# MCU_IO.net
KiCad netlist of a schematic drawn in Altium Designer
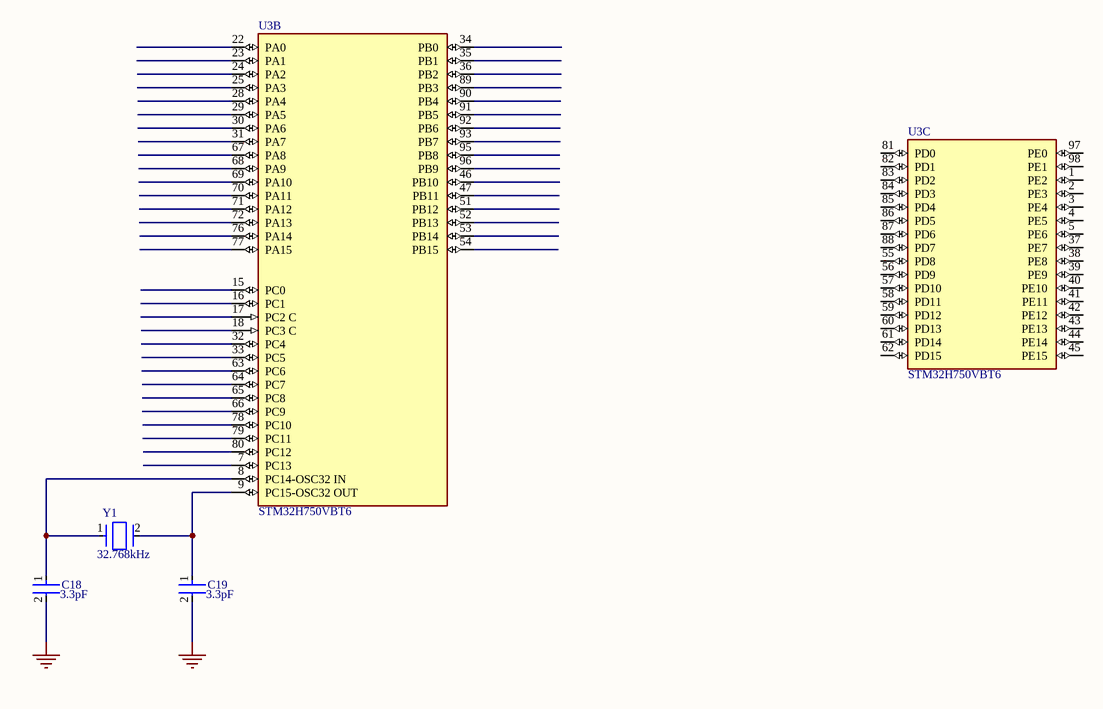
[diagram p0: MCU_IO.SchDoc]

(export (version "E")
  (design (tool "Eeschema 10.0.6"))
  (components
    (comp (ref "C18")
      (value "GCM1555C1H3R3CA16J")
      (footprint "FP-GCM155-0_05-IPC_C")
      (description "Ceramic Capacitor for Automotive 3.3pF ±0.25pF 50VDC C0G 0402 Paper T/R")
      (fields (field (name "CAPACITANCE") "3.3pF"))
      (libsource (lib "Altium Content Vault") (part "02cd4be3c70576c341d710602a673aa"))
    )
    (comp (ref "C19")
      (value "GCM1555C1H3R3CA16J")
      (footprint "FP-GCM155-0_05-IPC_C")
      (description "Ceramic Capacitor for Automotive 3.3pF ±0.25pF 50VDC C0G 0402 Paper T/R")
      (fields (field (name "CAPACITANCE") "3.3pF"))
      (libsource (lib "Altium Content Vault") (part "02cd4be3c70576c341d710602a673aa"))
    )
    (comp (ref "U3")
      (value "STM32H750VBT6")
      (footprint "FP-LQFP100-1L-MFG")
      (description "IC MCU 32BIT 128KB FLASH 100LQFP")
      (fields
        (field (name "OCTOPART") "https://octopart.com/stm32h750vbt6-stmicroelectronics-94048547")
        (field (name "MANUFACTURER") "STMicroelectronics")
      )
      (libsource (lib "Altium Content Vault") (part "aca449acb2b80670ba40d015d68dc7a"))
    )
    (comp (ref "Y1")
      (value "ECS-.327-6-34QCN-TR")
      (footprint "FP-ECX-34Q-MFG")
      (description "CRYSTAL 32.768KHZ 6PF SMD")
      (fields
        (field (name "OCTOPART") "https://octopart.com/ecs-.327-6-34qcn-tr-ecs+international-97157707")
        (field (name "MANUFACTURER") "ECS Inc.")
        (field (name "FREQUENCY") "32.768kHz")
      )
      (libsource (lib "Altium Content Vault") (part "99724985039315a44fd0d1401b84e49"))
    )
  )
  (nets
    (net (code "1") (name "GND") (class "Default")
      (node (ref "C18") (pin "2") (pinfunction "2_2") (pintype "passive"))
      (node (ref "C19") (pin "2") (pinfunction "2_2") (pintype "passive"))
    )
    (net (code "2") (name "Net-(U3B-PC14-OSC32_IN)") (class "Default")
      (node (ref "C18") (pin "1") (pinfunction "1_1") (pintype "passive"))
      (node (ref "U3") (pin "8") (pinfunction "PC14-OSC32_IN_8") (pintype "bidirectional"))
      (node (ref "Y1") (pin "1") (pinfunction "In/Out_1") (pintype "passive"))
    )
    (net (code "3") (name "Net-(U3B-PC15-OSC32_OUT)") (class "Default")
      (node (ref "C19") (pin "1") (pinfunction "1_1") (pintype "passive"))
      (node (ref "U3") (pin "9") (pinfunction "PC15-OSC32_OUT_9") (pintype "bidirectional"))
      (node (ref "Y1") (pin "2") (pinfunction "Out/In_2") (pintype "passive"))
    )
    (net (code "4") (name "unconnected-(U3B-PA0-Pad22)") (class "Default")
      (node (ref "U3") (pin "22") (pinfunction "PA0_22") (pintype "bidirectional"))
    )
    (net (code "5") (name "unconnected-(U3B-PA1-Pad23)") (class "Default")
      (node (ref "U3") (pin "23") (pinfunction "PA1_23") (pintype "bidirectional"))
    )
    (net (code "6") (name "unconnected-(U3B-PA2-Pad24)") (class "Default")
      (node (ref "U3") (pin "24") (pinfunction "PA2_24") (pintype "bidirectional"))
    )
    (net (code "7") (name "unconnected-(U3B-PA3-Pad25)") (class "Default")
      (node (ref "U3") (pin "25") (pinfunction "PA3_25") (pintype "bidirectional"))
    )
    (net (code "8") (name "unconnected-(U3B-PA4-Pad28)") (class "Default")
      (node (ref "U3") (pin "28") (pinfunction "PA4_28") (pintype "bidirectional"))
    )
    (net (code "9") (name "unconnected-(U3B-PA5-Pad29)") (class "Default")
      (node (ref "U3") (pin "29") (pinfunction "PA5_29") (pintype "bidirectional"))
    )
    (net (code "10") (name "unconnected-(U3B-PA6-Pad30)") (class "Default")
      (node (ref "U3") (pin "30") (pinfunction "PA6_30") (pintype "bidirectional"))
    )
    (net (code "11") (name "unconnected-(U3B-PA7-Pad31)") (class "Default")
      (node (ref "U3") (pin "31") (pinfunction "PA7_31") (pintype "bidirectional"))
    )
    (net (code "12") (name "unconnected-(U3B-PA8-Pad67)") (class "Default")
      (node (ref "U3") (pin "67") (pinfunction "PA8_67") (pintype "bidirectional"))
    )
    (net (code "13") (name "unconnected-(U3B-PA9-Pad68)") (class "Default")
      (node (ref "U3") (pin "68") (pinfunction "PA9_68") (pintype "bidirectional"))
    )
    (net (code "14") (name "unconnected-(U3B-PA10-Pad69)") (class "Default")
      (node (ref "U3") (pin "69") (pinfunction "PA10_69") (pintype "bidirectional"))
    )
    (net (code "15") (name "unconnected-(U3B-PA11-Pad70)") (class "Default")
      (node (ref "U3") (pin "70") (pinfunction "PA11_70") (pintype "bidirectional"))
    )
    (net (code "16") (name "unconnected-(U3B-PA12-Pad71)") (class "Default")
      (node (ref "U3") (pin "71") (pinfunction "PA12_71") (pintype "bidirectional"))
    )
    (net (code "17") (name "unconnected-(U3B-PA13-Pad72)") (class "Default")
      (node (ref "U3") (pin "72") (pinfunction "PA13_72") (pintype "bidirectional"))
    )
    (net (code "18") (name "unconnected-(U3B-PA14-Pad76)") (class "Default")
      (node (ref "U3") (pin "76") (pinfunction "PA14_76") (pintype "bidirectional"))
    )
    (net (code "19") (name "unconnected-(U3B-PA15-Pad77)") (class "Default")
      (node (ref "U3") (pin "77") (pinfunction "PA15_77") (pintype "bidirectional"))
    )
    (net (code "20") (name "unconnected-(U3B-PB0-Pad34)") (class "Default")
      (node (ref "U3") (pin "34") (pinfunction "PB0_34") (pintype "bidirectional"))
    )
    (net (code "21") (name "unconnected-(U3B-PB1-Pad35)") (class "Default")
      (node (ref "U3") (pin "35") (pinfunction "PB1_35") (pintype "bidirectional"))
    )
    (net (code "22") (name "unconnected-(U3B-PB2-Pad36)") (class "Default")
      (node (ref "U3") (pin "36") (pinfunction "PB2_36") (pintype "bidirectional"))
    )
    (net (code "23") (name "unconnected-(U3B-PB3-Pad89)") (class "Default")
      (node (ref "U3") (pin "89") (pinfunction "PB3_89") (pintype "bidirectional"))
    )
    (net (code "24") (name "unconnected-(U3B-PB4-Pad90)") (class "Default")
      (node (ref "U3") (pin "90") (pinfunction "PB4_90") (pintype "bidirectional"))
    )
    (net (code "25") (name "unconnected-(U3B-PB5-Pad91)") (class "Default")
      (node (ref "U3") (pin "91") (pinfunction "PB5_91") (pintype "bidirectional"))
    )
    (net (code "26") (name "unconnected-(U3B-PB6-Pad92)") (class "Default")
      (node (ref "U3") (pin "92") (pinfunction "PB6_92") (pintype "bidirectional"))
    )
    (net (code "27") (name "unconnected-(U3B-PB7-Pad93)") (class "Default")
      (node (ref "U3") (pin "93") (pinfunction "PB7_93") (pintype "bidirectional"))
    )
    (net (code "28") (name "unconnected-(U3B-PB8-Pad95)") (class "Default")
      (node (ref "U3") (pin "95") (pinfunction "PB8_95") (pintype "bidirectional"))
    )
    (net (code "29") (name "unconnected-(U3B-PB9-Pad96)") (class "Default")
      (node (ref "U3") (pin "96") (pinfunction "PB9_96") (pintype "bidirectional"))
    )
    (net (code "30") (name "unconnected-(U3B-PB10-Pad46)") (class "Default")
      (node (ref "U3") (pin "46") (pinfunction "PB10_46") (pintype "bidirectional"))
    )
    (net (code "31") (name "unconnected-(U3B-PB11-Pad47)") (class "Default")
      (node (ref "U3") (pin "47") (pinfunction "PB11_47") (pintype "bidirectional"))
    )
    (net (code "32") (name "unconnected-(U3B-PB12-Pad51)") (class "Default")
      (node (ref "U3") (pin "51") (pinfunction "PB12_51") (pintype "bidirectional"))
    )
    (net (code "33") (name "unconnected-(U3B-PB13-Pad52)") (class "Default")
      (node (ref "U3") (pin "52") (pinfunction "PB13_52") (pintype "bidirectional"))
    )
    (net (code "34") (name "unconnected-(U3B-PB14-Pad53)") (class "Default")
      (node (ref "U3") (pin "53") (pinfunction "PB14_53") (pintype "bidirectional"))
    )
    (net (code "35") (name "unconnected-(U3B-PB15-Pad54)") (class "Default")
      (node (ref "U3") (pin "54") (pinfunction "PB15_54") (pintype "bidirectional"))
    )
    (net (code "36") (name "unconnected-(U3B-PC0-Pad15)") (class "Default")
      (node (ref "U3") (pin "15") (pinfunction "PC0_15") (pintype "bidirectional"))
    )
    (net (code "37") (name "unconnected-(U3B-PC1-Pad16)") (class "Default")
      (node (ref "U3") (pin "16") (pinfunction "PC1_16") (pintype "bidirectional"))
    )
    (net (code "38") (name "unconnected-(U3B-PC2_C-Pad17)") (class "Default")
      (node (ref "U3") (pin "17") (pinfunction "PC2_C_17") (pintype "input"))
    )
    (net (code "39") (name "unconnected-(U3B-PC3_C-Pad18)") (class "Default")
      (node (ref "U3") (pin "18") (pinfunction "PC3_C_18") (pintype "input"))
    )
    (net (code "40") (name "unconnected-(U3B-PC4-Pad32)") (class "Default")
      (node (ref "U3") (pin "32") (pinfunction "PC4_32") (pintype "bidirectional"))
    )
    (net (code "41") (name "unconnected-(U3B-PC5-Pad33)") (class "Default")
      (node (ref "U3") (pin "33") (pinfunction "PC5_33") (pintype "bidirectional"))
    )
    (net (code "42") (name "unconnected-(U3B-PC6-Pad63)") (class "Default")
      (node (ref "U3") (pin "63") (pinfunction "PC6_63") (pintype "bidirectional"))
    )
    (net (code "43") (name "unconnected-(U3B-PC7-Pad64)") (class "Default")
      (node (ref "U3") (pin "64") (pinfunction "PC7_64") (pintype "bidirectional"))
    )
    (net (code "44") (name "unconnected-(U3B-PC8-Pad65)") (class "Default")
      (node (ref "U3") (pin "65") (pinfunction "PC8_65") (pintype "bidirectional"))
    )
    (net (code "45") (name "unconnected-(U3B-PC9-Pad66)") (class "Default")
      (node (ref "U3") (pin "66") (pinfunction "PC9_66") (pintype "bidirectional"))
    )
    (net (code "46") (name "unconnected-(U3B-PC10-Pad78)") (class "Default")
      (node (ref "U3") (pin "78") (pinfunction "PC10_78") (pintype "bidirectional"))
    )
    (net (code "47") (name "unconnected-(U3B-PC11-Pad79)") (class "Default")
      (node (ref "U3") (pin "79") (pinfunction "PC11_79") (pintype "bidirectional"))
    )
    (net (code "48") (name "unconnected-(U3B-PC12-Pad80)") (class "Default")
      (node (ref "U3") (pin "80") (pinfunction "PC12_80") (pintype "bidirectional"))
    )
    (net (code "49") (name "unconnected-(U3B-PC13-Pad7)") (class "Default")
      (node (ref "U3") (pin "7") (pinfunction "PC13_7") (pintype "bidirectional"))
    )
    (net (code "50") (name "unconnected-(U3C-PD0-Pad81)") (class "Default")
      (node (ref "U3") (pin "81") (pinfunction "PD0_81") (pintype "bidirectional"))
    )
    (net (code "51") (name "unconnected-(U3C-PD1-Pad82)") (class "Default")
      (node (ref "U3") (pin "82") (pinfunction "PD1_82") (pintype "bidirectional"))
    )
    (net (code "52") (name "unconnected-(U3C-PD2-Pad83)") (class "Default")
      (node (ref "U3") (pin "83") (pinfunction "PD2_83") (pintype "bidirectional"))
    )
    (net (code "53") (name "unconnected-(U3C-PD3-Pad84)") (class "Default")
      (node (ref "U3") (pin "84") (pinfunction "PD3_84") (pintype "bidirectional"))
    )
    (net (code "54") (name "unconnected-(U3C-PD4-Pad85)") (class "Default")
      (node (ref "U3") (pin "85") (pinfunction "PD4_85") (pintype "bidirectional"))
    )
    (net (code "55") (name "unconnected-(U3C-PD5-Pad86)") (class "Default")
      (node (ref "U3") (pin "86") (pinfunction "PD5_86") (pintype "bidirectional"))
    )
    (net (code "56") (name "unconnected-(U3C-PD6-Pad87)") (class "Default")
      (node (ref "U3") (pin "87") (pinfunction "PD6_87") (pintype "bidirectional"))
    )
    (net (code "57") (name "unconnected-(U3C-PD7-Pad88)") (class "Default")
      (node (ref "U3") (pin "88") (pinfunction "PD7_88") (pintype "bidirectional"))
    )
    (net (code "58") (name "unconnected-(U3C-PD8-Pad55)") (class "Default")
      (node (ref "U3") (pin "55") (pinfunction "PD8_55") (pintype "bidirectional"))
    )
    (net (code "59") (name "unconnected-(U3C-PD9-Pad56)") (class "Default")
      (node (ref "U3") (pin "56") (pinfunction "PD9_56") (pintype "bidirectional"))
    )
    (net (code "60") (name "unconnected-(U3C-PD10-Pad57)") (class "Default")
      (node (ref "U3") (pin "57") (pinfunction "PD10_57") (pintype "bidirectional"))
    )
    (net (code "61") (name "unconnected-(U3C-PD11-Pad58)") (class "Default")
      (node (ref "U3") (pin "58") (pinfunction "PD11_58") (pintype "bidirectional"))
    )
    (net (code "62") (name "unconnected-(U3C-PD12-Pad59)") (class "Default")
      (node (ref "U3") (pin "59") (pinfunction "PD12_59") (pintype "bidirectional"))
    )
    (net (code "63") (name "unconnected-(U3C-PD13-Pad60)") (class "Default")
      (node (ref "U3") (pin "60") (pinfunction "PD13_60") (pintype "bidirectional"))
    )
    (net (code "64") (name "unconnected-(U3C-PD14-Pad61)") (class "Default")
      (node (ref "U3") (pin "61") (pinfunction "PD14_61") (pintype "bidirectional"))
    )
    (net (code "65") (name "unconnected-(U3C-PD15-Pad62)") (class "Default")
      (node (ref "U3") (pin "62") (pinfunction "PD15_62") (pintype "bidirectional"))
    )
    (net (code "66") (name "unconnected-(U3C-PE0-Pad97)") (class "Default")
      (node (ref "U3") (pin "97") (pinfunction "PE0_97") (pintype "bidirectional"))
    )
    (net (code "67") (name "unconnected-(U3C-PE1-Pad98)") (class "Default")
      (node (ref "U3") (pin "98") (pinfunction "PE1_98") (pintype "bidirectional"))
    )
    (net (code "68") (name "unconnected-(U3C-PE2-Pad1)") (class "Default")
      (node (ref "U3") (pin "1") (pinfunction "PE2_1") (pintype "bidirectional"))
    )
    (net (code "69") (name "unconnected-(U3C-PE3-Pad2)") (class "Default")
      (node (ref "U3") (pin "2") (pinfunction "PE3_2") (pintype "bidirectional"))
    )
    (net (code "70") (name "unconnected-(U3C-PE4-Pad3)") (class "Default")
      (node (ref "U3") (pin "3") (pinfunction "PE4_3") (pintype "bidirectional"))
    )
    (net (code "71") (name "unconnected-(U3C-PE5-Pad4)") (class "Default")
      (node (ref "U3") (pin "4") (pinfunction "PE5_4") (pintype "bidirectional"))
    )
    (net (code "72") (name "unconnected-(U3C-PE6-Pad5)") (class "Default")
      (node (ref "U3") (pin "5") (pinfunction "PE6_5") (pintype "bidirectional"))
    )
    (net (code "73") (name "unconnected-(U3C-PE7-Pad37)") (class "Default")
      (node (ref "U3") (pin "37") (pinfunction "PE7_37") (pintype "bidirectional"))
    )
    (net (code "74") (name "unconnected-(U3C-PE8-Pad38)") (class "Default")
      (node (ref "U3") (pin "38") (pinfunction "PE8_38") (pintype "bidirectional"))
    )
    (net (code "75") (name "unconnected-(U3C-PE9-Pad39)") (class "Default")
      (node (ref "U3") (pin "39") (pinfunction "PE9_39") (pintype "bidirectional"))
    )
    (net (code "76") (name "unconnected-(U3C-PE10-Pad40)") (class "Default")
      (node (ref "U3") (pin "40") (pinfunction "PE10_40") (pintype "bidirectional"))
    )
    (net (code "77") (name "unconnected-(U3C-PE11-Pad41)") (class "Default")
      (node (ref "U3") (pin "41") (pinfunction "PE11_41") (pintype "bidirectional"))
    )
    (net (code "78") (name "unconnected-(U3C-PE12-Pad42)") (class "Default")
      (node (ref "U3") (pin "42") (pinfunction "PE12_42") (pintype "bidirectional"))
    )
    (net (code "79") (name "unconnected-(U3C-PE13-Pad43)") (class "Default")
      (node (ref "U3") (pin "43") (pinfunction "PE13_43") (pintype "bidirectional"))
    )
    (net (code "80") (name "unconnected-(U3C-PE14-Pad44)") (class "Default")
      (node (ref "U3") (pin "44") (pinfunction "PE14_44") (pintype "bidirectional"))
    )
    (net (code "81") (name "unconnected-(U3C-PE15-Pad45)") (class "Default")
      (node (ref "U3") (pin "45") (pinfunction "PE15_45") (pintype "bidirectional"))
    )
  )
)
